# Amplifier.net
KiCad netlist of a schematic drawn in Altium Designer
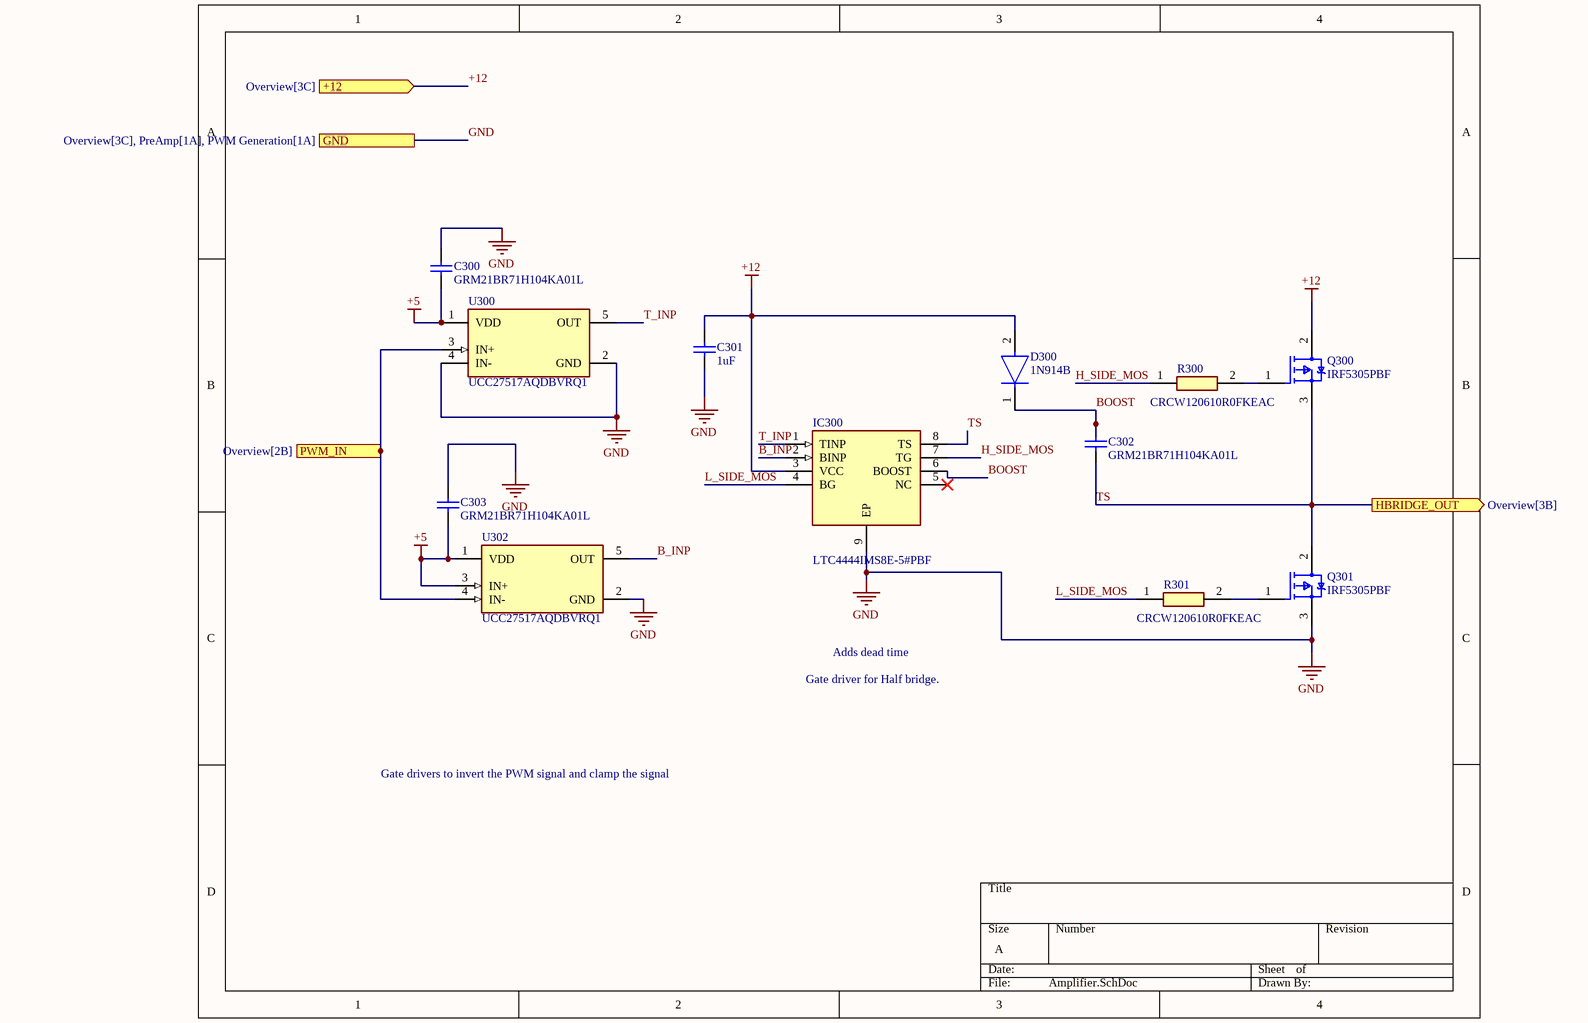
[diagram p0: Amplifier.SchDoc]

(export (version "E")
  (design (tool "Eeschema 10.0.6"))
  (components
    (comp (ref "C300")
      (value "GRM21BR71H104KA01L")
      (footprint "CAPC2013X135X45ML10T25")
      (description "Chip Capacitor, 0.1 uF, +/- 10%, 50 V, -55 to 125 degC, 0805 (2012 Metric), RoHS, Tape and Reel")
      (fields (field (name "VOLTAGE") "50V") (field (name "TOLERANCE") "10%"))
      (libsource (lib "Altium Content Vault") (part "CAP-NP-2"))
    )
    (comp (ref "C301")
      (value "1uF")
      (footprint "CAPC2013X140X50LL20T25")
      (description "C0805C105K3RACTU")
      (fields (field (name "MANUFACTURER") "Kemet"))
      (libsource (lib "Altium Content Vault") (part "CAP"))
    )
    (comp (ref "C302")
      (value "GRM21BR71H104KA01L")
      (footprint "CAPC2013X135X45ML10T25")
      (description "Chip Capacitor, 0.1 uF, +/- 10%, 50 V, -55 to 125 degC, 0805 (2012 Metric), RoHS, Tape and Reel")
      (fields (field (name "VOLTAGE") "50V") (field (name "TOLERANCE") "10%"))
      (libsource (lib "Altium Content Vault") (part "CAP-NP-2"))
    )
    (comp (ref "C303")
      (value "GRM21BR71H104KA01L")
      (footprint "CAPC2013X135X45ML10T25")
      (description "Chip Capacitor, 0.1 uF, +/- 10%, 50 V, -55 to 125 degC, 0805 (2012 Metric), RoHS, Tape and Reel")
      (fields (field (name "VOLTAGE") "50V") (field (name "TOLERANCE") "10%"))
      (libsource (lib "Altium Content Vault") (part "CAP-NP-2"))
    )
    (comp (ref "D300")
      (value "1N914B")
      (footprint "FP-017AG-MFG")
      (description "DIODE GEN PURP 100V 200MA DO35")
      (fields
        (field (name "OCTOPART") "https://octopart.com/1n914b-on+semiconductor-84323163")
        (field (name "MANUFACTURER") "ON Semiconductor")
      )
      (libsource (lib "Altium Content Vault") (part "d7152d700b627762746794eb795d46e"))
    )
    (comp (ref "IC300")
      (value "LTC4444IMS8E-5#PBF")
      (footprint "SamacSys:SOP65P490X110-9N")
      (description "Integrated Circuit")
      (fields (field (name "MOUSER PART NUMBER") "584-C4444IMS8E-5PBF"))
      (libsource (lib "*") (part "LTC4444IMS8E-5#PBF"))
    )
    (comp (ref "Q300")
      (value "IRF5305PBF")
      (footprint "FP-PG-TO220-3-0")
      (description "MOSFET P-CH 55V 31A TO-220AB")
      (fields
        (field (name "OCTOPART") "https://octopart.com/irf5305pbf-infineon-65873396")
        (field (name "MANUFACTURER") "Infineon")
      )
      (libsource (lib "Altium Content Vault") (part "ef9d0aacdf366ab529cd174aea9d313"))
    )
    (comp (ref "Q301")
      (value "IRF5305PBF")
      (footprint "FP-PG-TO220-3-0")
      (description "MOSFET P-CH 55V 31A TO-220AB")
      (fields
        (field (name "OCTOPART") "https://octopart.com/irf5305pbf-infineon-65873396")
        (field (name "MANUFACTURER") "Infineon")
      )
      (libsource (lib "Altium Content Vault") (part "ef9d0aacdf366ab529cd174aea9d313"))
    )
    (comp (ref "R300")
      (value "CRCW120610R0FKEAC")
      (footprint "SamacSys:RESC3216X60N")
      (description "Resistor")
      (fields (field (name "MOUSER PART NUMBER") "71-CRCW120610R0FKEAC"))
      (libsource (lib "*") (part "CRCW120610R0FKEAC"))
    )
    (comp (ref "R301")
      (value "CRCW120610R0FKEAC")
      (footprint "SamacSys:RESC3216X60N")
      (description "Resistor")
      (fields (field (name "MOUSER PART NUMBER") "71-CRCW120610R0FKEAC"))
      (libsource (lib "*") (part "CRCW120610R0FKEAC"))
    )
    (comp (ref "U300")
      (value "UCC27517AQDBVRQ1")
      (footprint "FP-DBV0005A-IPC_B")
      (description "IC GATE DVR LOW SIDE 1CH SOT23-5")
      (libsource (lib "Altium Content Vault") (part "852976a250a43ce973e2ce06d98181f"))
    )
    (comp (ref "U302")
      (value "UCC27517AQDBVRQ1")
      (footprint "FP-DBV0005A-IPC_B")
      (description "IC GATE DVR LOW SIDE 1CH SOT23-5")
      (libsource (lib "Altium Content Vault") (part "852976a250a43ce973e2ce06d98181f"))
    )
  )
  (nets
    (net (code "1") (name "+5") (class "Default")
      (node (ref "C300") (pin "1") (pinfunction "1_1") (pintype "passive"))
      (node (ref "C303") (pin "1") (pinfunction "1_1") (pintype "passive"))
      (node (ref "U300") (pin "1") (pinfunction "VDD_1") (pintype "passive"))
      (node (ref "U302") (pin "1") (pinfunction "VDD_1") (pintype "passive"))
      (node (ref "U302") (pin "3") (pinfunction "IN+_3") (pintype "input"))
    )
    (net (code "2") (name "+12") (class "Default")
      (node (ref "C301") (pin "1") (pinfunction "1_1") (pintype "passive"))
      (node (ref "D300") (pin "2") (pinfunction "A_2") (pintype "passive"))
      (node (ref "IC300") (pin "3") (pinfunction "VCC_3") (pintype "passive"))
      (node (ref "Q300") (pin "2") (pinfunction "D_2") (pintype "passive"))
    )
    (net (code "3") (name "/BOOST") (class "Default")
      (node (ref "C302") (pin "2") (pinfunction "2_2") (pintype "passive"))
      (node (ref "D300") (pin "1") (pinfunction "C_1") (pintype "passive"))
      (node (ref "IC300") (pin "6") (pinfunction "BOOST_6") (pintype "passive"))
    )
    (net (code "4") (name "/B_INP") (class "Default")
      (node (ref "IC300") (pin "2") (pinfunction "BINP_2") (pintype "input"))
      (node (ref "U302") (pin "5") (pinfunction "OUT_5") (pintype "passive"))
    )
    (net (code "5") (name "/H_SIDE_MOS") (class "Default")
      (node (ref "IC300") (pin "7") (pinfunction "TG_7") (pintype "passive"))
      (node (ref "R300") (pin "1") (pinfunction "1_1") (pintype "passive"))
    )
    (net (code "6") (name "/L_SIDE_MOS") (class "Default")
      (node (ref "IC300") (pin "4") (pinfunction "BG_4") (pintype "passive"))
      (node (ref "R301") (pin "1") (pinfunction "1_1") (pintype "passive"))
    )
    (net (code "7") (name "/PWM_IN") (class "Default")
      (node (ref "U300") (pin "3") (pinfunction "IN+_3") (pintype "input"))
      (node (ref "U302") (pin "4") (pinfunction "IN-_4") (pintype "passive"))
    )
    (net (code "8") (name "/TS") (class "Default")
      (node (ref "C302") (pin "1") (pinfunction "1_1") (pintype "passive"))
      (node (ref "IC300") (pin "8") (pinfunction "TS_8") (pintype "passive"))
      (node (ref "Q300") (pin "3") (pinfunction "S_3") (pintype "passive"))
      (node (ref "Q301") (pin "2") (pinfunction "D_2") (pintype "passive"))
    )
    (net (code "9") (name "/T_INP") (class "Default")
      (node (ref "IC300") (pin "1") (pinfunction "TINP_1") (pintype "input"))
      (node (ref "U300") (pin "5") (pinfunction "OUT_5") (pintype "passive"))
    )
    (net (code "10") (name "GND") (class "Default")
      (node (ref "C300") (pin "2") (pinfunction "2_2") (pintype "passive"))
      (node (ref "C301") (pin "2") (pinfunction "2_2") (pintype "passive"))
      (node (ref "C303") (pin "2") (pinfunction "2_2") (pintype "passive"))
      (node (ref "IC300") (pin "9") (pinfunction "EP_9") (pintype "power_in"))
      (node (ref "Q301") (pin "3") (pinfunction "S_3") (pintype "passive"))
      (node (ref "U300") (pin "2") (pinfunction "GND_2") (pintype "passive"))
      (node (ref "U300") (pin "4") (pinfunction "IN-_4") (pintype "passive"))
      (node (ref "U302") (pin "2") (pinfunction "GND_2") (pintype "passive"))
    )
    (net (code "11") (name "Net-(Q300-G)") (class "Default")
      (node (ref "Q300") (pin "1") (pinfunction "G_1") (pintype "passive"))
      (node (ref "R300") (pin "2") (pinfunction "2_2") (pintype "passive"))
    )
    (net (code "12") (name "Net-(Q301-G)") (class "Default")
      (node (ref "Q301") (pin "1") (pinfunction "G_1") (pintype "passive"))
      (node (ref "R301") (pin "2") (pinfunction "2_2") (pintype "passive"))
    )
    (net (code "13") (name "unconnected-(IC300-NC-Pad5)") (class "Default")
      (node (ref "IC300") (pin "5") (pinfunction "NC_5") (pintype "passive+no_connect"))
    )
  )
)
